# optoshield3.net
KiCad netlist of a schematic drawn in EAGLE
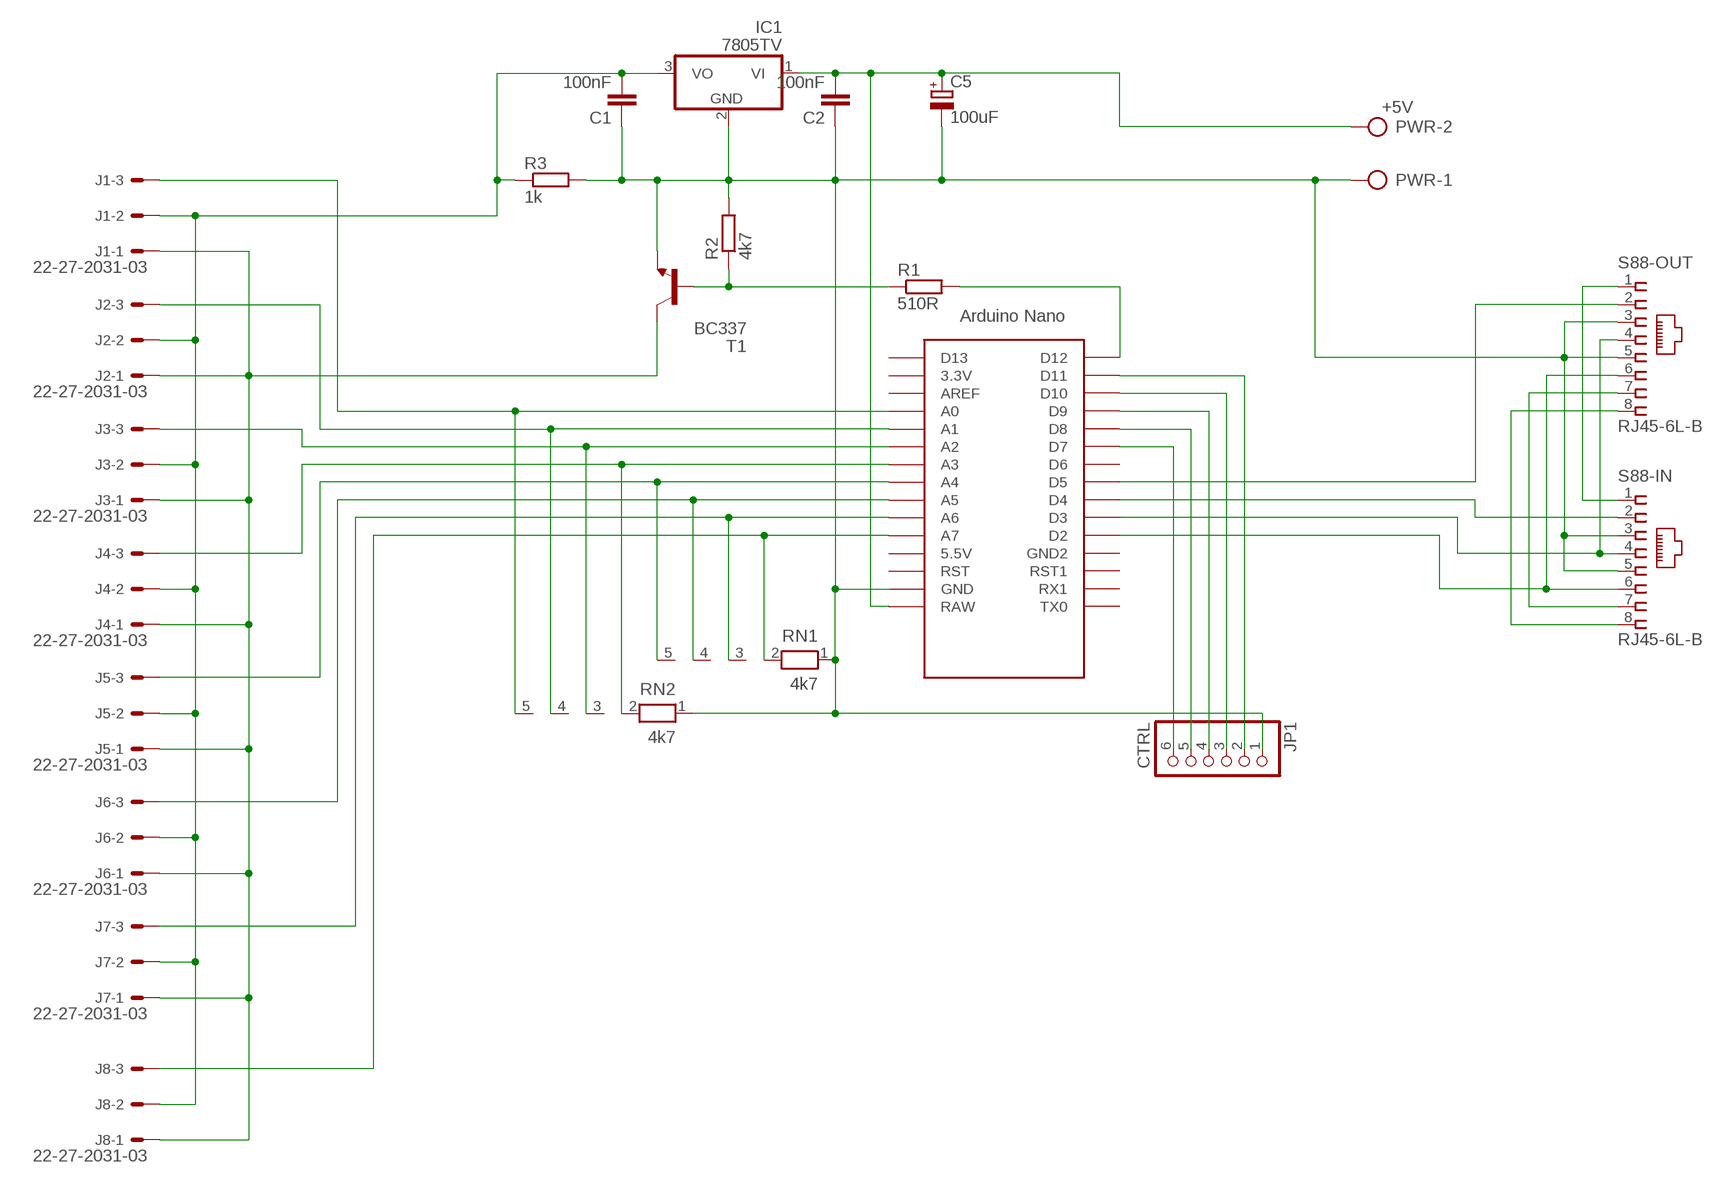
[diagram p0: schematic, sheet 1]

(export (version "E")
  (design (tool "Eeschema 10.0.6"))
  (components
    (comp (ref "C1")
      (value "100nF")
      (footprint "eagle-import:C025-025X050")
      (libsource (lib "eagle-import") (part "C-EU025-025X050"))
    )
    (comp (ref "C2")
      (value "100nF")
      (footprint "eagle-import:C025-025X050")
      (libsource (lib "eagle-import") (part "C-EU025-025X050"))
    )
    (comp (ref "C5")
      (value "100uF")
      (footprint "eagle-import:E3,5-10")
      (libsource (lib "eagle-import") (part "CPOL-EUE3.5-10"))
    )
    (comp (ref "IC1")
      (value "7805TV")
      (footprint "eagle-import:TO220V")
      (libsource (lib "eagle-import") (part "78TV05"))
    )
    (comp (ref "J1")
      (value "22-27-2031-03")
      (footprint "eagle-import:6410-03")
      (libsource (lib "eagle-import") (part "22-?-0327-2031"))
    )
    (comp (ref "J2")
      (value "22-27-2031-03")
      (footprint "eagle-import:6410-03")
      (libsource (lib "eagle-import") (part "22-?-0327-2031"))
    )
    (comp (ref "J3")
      (value "22-27-2031-03")
      (footprint "eagle-import:6410-03")
      (libsource (lib "eagle-import") (part "22-?-0327-2031"))
    )
    (comp (ref "J4")
      (value "22-27-2031-03")
      (footprint "eagle-import:6410-03")
      (libsource (lib "eagle-import") (part "22-?-0327-2031"))
    )
    (comp (ref "J5")
      (value "22-27-2031-03")
      (footprint "eagle-import:6410-03")
      (libsource (lib "eagle-import") (part "22-?-0327-2031"))
    )
    (comp (ref "J6")
      (value "22-27-2031-03")
      (footprint "eagle-import:6410-03")
      (libsource (lib "eagle-import") (part "22-?-0327-2031"))
    )
    (comp (ref "J7")
      (value "22-27-2031-03")
      (footprint "eagle-import:6410-03")
      (libsource (lib "eagle-import") (part "22-?-0327-2031"))
    )
    (comp (ref "J8")
      (value "22-27-2031-03")
      (footprint "eagle-import:6410-03")
      (libsource (lib "eagle-import") (part "22-?-0327-2031"))
    )
    (comp (ref "JP1")
      (value "CTRL")
      (footprint "eagle-import:1X06")
      (libsource (lib "eagle-import") (part "PINHD-1X6"))
    )
    (comp (ref "PWR")
      (value "+5V")
      (footprint "eagle-import:AK500_2")
      (libsource (lib "eagle-import") (part "AK500/2"))
    )
    (comp (ref "R1")
      (value "510R")
      (footprint "eagle-import:0207_10")
      (libsource (lib "eagle-import") (part "R-EU_0207/10"))
    )
    (comp (ref "R2")
      (value "4k7")
      (footprint "eagle-import:0207_10")
      (libsource (lib "eagle-import") (part "R-EU_0207/10"))
    )
    (comp (ref "R3")
      (value "1k")
      (footprint "eagle-import:0207_10")
      (libsource (lib "eagle-import") (part "resistor_R-EU_0207/10"))
    )
    (comp (ref "RN1")
      (value "4k7")
      (footprint "eagle-import:RN-5")
      (libsource (lib "eagle-import") (part "RN04"))
    )
    (comp (ref "RN2")
      (value "4k7")
      (footprint "eagle-import:RN-5")
      (libsource (lib "eagle-import") (part "RN04"))
    )
    (comp (ref "S88-IN")
      (value "RJ45-6L-B")
      (footprint "eagle-import:RJ45-NO-SHIELD")
      (libsource (lib "eagle-import") (part "RJ45-6L-B"))
    )
    (comp (ref "S88-OUT")
      (value "RJ45-6L-B")
      (footprint "eagle-import:RJ45-NO-SHIELD")
      (libsource (lib "eagle-import") (part "RJ45-6L-B"))
    )
    (comp (ref "T1")
      (value "BC337")
      (footprint "eagle-import:TO92")
      (libsource (lib "eagle-import") (part "BC337"))
    )
    (comp (ref "U$1")
      (value "NANO")
      (footprint "eagle-import:NANO")
      (libsource (lib "eagle-import") (part "NANO"))
    )
  )
  (nets
    (net (code "1") (name "Net-(IC1-GND)") (class "Default")
      (node (ref "C1") (pin "1") (pinfunction "1_1") (pintype "passive"))
      (node (ref "C2") (pin "1") (pinfunction "1_1") (pintype "passive"))
      (node (ref "C5") (pin "-") (pinfunction "-_-") (pintype "passive"))
      (node (ref "IC1") (pin "2") (pinfunction "GND_2") (pintype "passive"))
      (node (ref "JP1") (pin "1") (pinfunction "1_1") (pintype "passive"))
      (node (ref "PWR") (pin "1") (pinfunction "KL_1") (pintype "passive"))
      (node (ref "R2") (pin "2") (pinfunction "2_2") (pintype "passive"))
      (node (ref "R3") (pin "2") (pinfunction "2_2") (pintype "passive"))
      (node (ref "RN1") (pin "1") (pinfunction "1_1") (pintype "passive"))
      (node (ref "RN2") (pin "1") (pinfunction "1_1") (pintype "passive"))
      (node (ref "S88-IN") (pin "3") (pinfunction "3_3") (pintype "passive"))
      (node (ref "S88-IN") (pin "5") (pinfunction "5_5") (pintype "passive"))
      (node (ref "S88-OUT") (pin "3") (pinfunction "3_3") (pintype "passive"))
      (node (ref "S88-OUT") (pin "5") (pinfunction "5_5") (pintype "passive"))
      (node (ref "T1") (pin "1") (pinfunction "E_1") (pintype "passive"))
      (node (ref "U$1") (pin "GND") (pinfunction "GND_GND") (pintype "bidirectional"))
    )
    (net (code "2") (name "Net-(IC1-VI)") (class "Default")
      (node (ref "C2") (pin "2") (pinfunction "2_2") (pintype "passive"))
      (node (ref "C5") (pin "+") (pinfunction "+_+") (pintype "passive"))
      (node (ref "IC1") (pin "1") (pinfunction "VI_1") (pintype "input"))
      (node (ref "PWR") (pin "2") (pinfunction "KL_2") (pintype "passive"))
      (node (ref "U$1") (pin "RAW") (pinfunction "RAW_RAW") (pintype "bidirectional"))
    )
    (net (code "3") (name "Net-(IC1-VO)") (class "Default")
      (node (ref "C1") (pin "2") (pinfunction "2_2") (pintype "passive"))
      (node (ref "IC1") (pin "3") (pinfunction "VO_3") (pintype "passive"))
      (node (ref "J1") (pin "2") (pinfunction "S_2") (pintype "passive"))
      (node (ref "J2") (pin "2") (pinfunction "S_2") (pintype "passive"))
      (node (ref "J3") (pin "2") (pinfunction "S_2") (pintype "passive"))
      (node (ref "J4") (pin "2") (pinfunction "S_2") (pintype "passive"))
      (node (ref "J5") (pin "2") (pinfunction "S_2") (pintype "passive"))
      (node (ref "J6") (pin "2") (pinfunction "S_2") (pintype "passive"))
      (node (ref "J7") (pin "2") (pinfunction "S_2") (pintype "passive"))
      (node (ref "J8") (pin "2") (pinfunction "S_2") (pintype "passive"))
      (node (ref "R3") (pin "1") (pinfunction "1_1") (pintype "passive"))
    )
    (net (code "4") (name "Net-(J1A-S)") (class "Default")
      (node (ref "J1") (pin "1") (pinfunction "S_1") (pintype "passive"))
      (node (ref "J2") (pin "1") (pinfunction "S_1") (pintype "passive"))
      (node (ref "J3") (pin "1") (pinfunction "S_1") (pintype "passive"))
      (node (ref "J4") (pin "1") (pinfunction "S_1") (pintype "passive"))
      (node (ref "J5") (pin "1") (pinfunction "S_1") (pintype "passive"))
      (node (ref "J6") (pin "1") (pinfunction "S_1") (pintype "passive"))
      (node (ref "J7") (pin "1") (pinfunction "S_1") (pintype "passive"))
      (node (ref "J8") (pin "1") (pinfunction "S_1") (pintype "passive"))
      (node (ref "T1") (pin "3") (pinfunction "C_3") (pintype "passive"))
    )
    (net (code "5") (name "Net-(J1C-S)") (class "Default")
      (node (ref "J1") (pin "3") (pinfunction "S_3") (pintype "passive"))
      (node (ref "RN2") (pin "5") (pinfunction "5_5") (pintype "passive"))
      (node (ref "U$1") (pin "A0") (pinfunction "A0_A0") (pintype "bidirectional"))
    )
    (net (code "6") (name "Net-(J2C-S)") (class "Default")
      (node (ref "J2") (pin "3") (pinfunction "S_3") (pintype "passive"))
      (node (ref "RN2") (pin "4") (pinfunction "4_4") (pintype "passive"))
      (node (ref "U$1") (pin "A1") (pinfunction "A1_A1") (pintype "bidirectional"))
    )
    (net (code "7") (name "Net-(J3C-S)") (class "Default")
      (node (ref "J3") (pin "3") (pinfunction "S_3") (pintype "passive"))
      (node (ref "RN2") (pin "3") (pinfunction "3_3") (pintype "passive"))
      (node (ref "U$1") (pin "A2") (pinfunction "A2_A2") (pintype "bidirectional"))
    )
    (net (code "8") (name "Net-(J4C-S)") (class "Default")
      (node (ref "J4") (pin "3") (pinfunction "S_3") (pintype "passive"))
      (node (ref "RN2") (pin "2") (pinfunction "2_2") (pintype "passive"))
      (node (ref "U$1") (pin "A3") (pinfunction "A3_A3") (pintype "bidirectional"))
    )
    (net (code "9") (name "Net-(J5C-S)") (class "Default")
      (node (ref "J5") (pin "3") (pinfunction "S_3") (pintype "passive"))
      (node (ref "RN1") (pin "5") (pinfunction "5_5") (pintype "passive"))
      (node (ref "U$1") (pin "A4") (pinfunction "A4_A4") (pintype "bidirectional"))
    )
    (net (code "10") (name "Net-(J6C-S)") (class "Default")
      (node (ref "J6") (pin "3") (pinfunction "S_3") (pintype "passive"))
      (node (ref "RN1") (pin "4") (pinfunction "4_4") (pintype "passive"))
      (node (ref "U$1") (pin "A5") (pinfunction "A5_A5") (pintype "bidirectional"))
    )
    (net (code "11") (name "Net-(J7C-S)") (class "Default")
      (node (ref "J7") (pin "3") (pinfunction "S_3") (pintype "passive"))
      (node (ref "RN1") (pin "3") (pinfunction "3_3") (pintype "passive"))
      (node (ref "U$1") (pin "A6") (pinfunction "A6_A6") (pintype "bidirectional"))
    )
    (net (code "12") (name "Net-(J8C-S)") (class "Default")
      (node (ref "J8") (pin "3") (pinfunction "S_3") (pintype "passive"))
      (node (ref "RN1") (pin "2") (pinfunction "2_2") (pintype "passive"))
      (node (ref "U$1") (pin "A7") (pinfunction "A7_A7") (pintype "bidirectional"))
    )
    (net (code "13") (name "Net-(JP1-Pad2)") (class "Default")
      (node (ref "JP1") (pin "2") (pinfunction "2_2") (pintype "passive"))
      (node (ref "U$1") (pin "D11") (pinfunction "D11_D11") (pintype "bidirectional"))
    )
    (net (code "14") (name "Net-(JP1-Pad3)") (class "Default")
      (node (ref "JP1") (pin "3") (pinfunction "3_3") (pintype "passive"))
      (node (ref "U$1") (pin "D10") (pinfunction "D10_D10") (pintype "bidirectional"))
    )
    (net (code "15") (name "Net-(JP1-Pad4)") (class "Default")
      (node (ref "JP1") (pin "4") (pinfunction "4_4") (pintype "passive"))
      (node (ref "U$1") (pin "D9") (pinfunction "D9_D9") (pintype "bidirectional"))
    )
    (net (code "16") (name "Net-(JP1-Pad5)") (class "Default")
      (node (ref "JP1") (pin "5") (pinfunction "5_5") (pintype "passive"))
      (node (ref "U$1") (pin "D8") (pinfunction "D8_D8") (pintype "bidirectional"))
    )
    (net (code "17") (name "Net-(JP1-Pad6)") (class "Default")
      (node (ref "JP1") (pin "6") (pinfunction "6_6") (pintype "passive"))
      (node (ref "U$1") (pin "D7") (pinfunction "D7_D7") (pintype "bidirectional"))
    )
    (net (code "18") (name "Net-(R1-Pad2)") (class "Default")
      (node (ref "R1") (pin "2") (pinfunction "2_2") (pintype "passive"))
      (node (ref "U$1") (pin "D12") (pinfunction "D12_D12") (pintype "bidirectional"))
    )
    (net (code "19") (name "Net-(S88-IN-Pad1)") (class "Default")
      (node (ref "S88-IN") (pin "1") (pinfunction "1_1") (pintype "passive"))
      (node (ref "S88-OUT") (pin "1") (pinfunction "1_1") (pintype "passive"))
    )
    (net (code "20") (name "Net-(S88-IN-Pad2)") (class "Default")
      (node (ref "S88-IN") (pin "2") (pinfunction "2_2") (pintype "passive"))
      (node (ref "U$1") (pin "D4") (pinfunction "D4_D4") (pintype "bidirectional"))
    )
    (net (code "21") (name "Net-(S88-IN-Pad4)") (class "Default")
      (node (ref "S88-IN") (pin "4") (pinfunction "4_4") (pintype "passive"))
      (node (ref "S88-OUT") (pin "4") (pinfunction "4_4") (pintype "passive"))
      (node (ref "U$1") (pin "D3") (pinfunction "D3_D3") (pintype "bidirectional"))
    )
    (net (code "22") (name "Net-(S88-IN-Pad6)") (class "Default")
      (node (ref "S88-IN") (pin "6") (pinfunction "6_6") (pintype "passive"))
      (node (ref "S88-OUT") (pin "6") (pinfunction "6_6") (pintype "passive"))
      (node (ref "U$1") (pin "D2") (pinfunction "D2_D2") (pintype "bidirectional"))
    )
    (net (code "23") (name "Net-(S88-IN-Pad7)") (class "Default")
      (node (ref "S88-IN") (pin "7") (pinfunction "7_7") (pintype "passive"))
      (node (ref "S88-OUT") (pin "7") (pinfunction "7_7") (pintype "passive"))
    )
    (net (code "24") (name "Net-(S88-IN-Pad8)") (class "Default")
      (node (ref "S88-IN") (pin "8") (pinfunction "8_8") (pintype "passive"))
      (node (ref "S88-OUT") (pin "8") (pinfunction "8_8") (pintype "passive"))
    )
    (net (code "25") (name "Net-(S88-OUT-Pad2)") (class "Default")
      (node (ref "S88-OUT") (pin "2") (pinfunction "2_2") (pintype "passive"))
      (node (ref "U$1") (pin "D5") (pinfunction "D5_D5") (pintype "bidirectional"))
    )
    (net (code "26") (name "Net-(T1-B)") (class "Default")
      (node (ref "R1") (pin "1") (pinfunction "1_1") (pintype "passive"))
      (node (ref "R2") (pin "1") (pinfunction "1_1") (pintype "passive"))
      (node (ref "T1") (pin "2") (pinfunction "B_2") (pintype "passive"))
    )
    (net (code "27") (name "unconnected-(U$1-5.5V-Pad5V)") (class "Default")
      (node (ref "U$1") (pin "5V") (pinfunction "5.5V_5V") (pintype "bidirectional"))
    )
    (net (code "28") (name "unconnected-(U$1-GND2-PadGND1)") (class "Default")
      (node (ref "U$1") (pin "GND1") (pinfunction "GND2_GND1") (pintype "bidirectional"))
    )
    (net (code "29") (name "unconnected-(U$1-Pad3.3V)") (class "Default")
      (node (ref "U$1") (pin "3.3V") (pinfunction "3.3V_3.3V") (pintype "bidirectional"))
    )
    (net (code "30") (name "unconnected-(U$1-PadAREF)") (class "Default")
      (node (ref "U$1") (pin "AREF") (pinfunction "AREF_AREF") (pintype "bidirectional"))
    )
    (net (code "31") (name "unconnected-(U$1-PadD6)") (class "Default")
      (node (ref "U$1") (pin "D6") (pinfunction "D6_D6") (pintype "bidirectional"))
    )
    (net (code "32") (name "unconnected-(U$1-PadD13)") (class "Default")
      (node (ref "U$1") (pin "D13") (pinfunction "D13_D13") (pintype "bidirectional"))
    )
    (net (code "33") (name "unconnected-(U$1-PadICSP1)") (class "Default")
      (node (ref "U$1") (pin "ICSP1") (pinfunction "ICSP1_ICSP1") (pintype "bidirectional"))
    )
    (net (code "34") (name "unconnected-(U$1-PadICSP2)") (class "Default")
      (node (ref "U$1") (pin "ICSP2") (pinfunction "ICSP2_ICSP2") (pintype "bidirectional"))
    )
    (net (code "35") (name "unconnected-(U$1-PadICSP3)") (class "Default")
      (node (ref "U$1") (pin "ICSP3") (pinfunction "ICSP3_ICSP3") (pintype "bidirectional"))
    )
    (net (code "36") (name "unconnected-(U$1-PadICSP4)") (class "Default")
      (node (ref "U$1") (pin "ICSP4") (pinfunction "ICSP4_ICSP4") (pintype "bidirectional"))
    )
    (net (code "37") (name "unconnected-(U$1-PadICSP5)") (class "Default")
      (node (ref "U$1") (pin "ICSP5") (pinfunction "ICSP5_ICSP5") (pintype "bidirectional"))
    )
    (net (code "38") (name "unconnected-(U$1-PadICSP6)") (class "Default")
      (node (ref "U$1") (pin "ICSP6") (pinfunction "ICSP6_ICSP6") (pintype "bidirectional"))
    )
    (net (code "39") (name "unconnected-(U$1-PadRST)") (class "Default")
      (node (ref "U$1") (pin "RST") (pinfunction "RST_RST") (pintype "bidirectional"))
    )
    (net (code "40") (name "unconnected-(U$1-PadRST1)") (class "Default")
      (node (ref "U$1") (pin "RST1") (pinfunction "RST1_RST1") (pintype "bidirectional"))
    )
    (net (code "41") (name "unconnected-(U$1-PadRX1)") (class "Default")
      (node (ref "U$1") (pin "RX1") (pinfunction "RX1_RX1") (pintype "bidirectional"))
    )
    (net (code "42") (name "unconnected-(U$1-PadTX0)") (class "Default")
      (node (ref "U$1") (pin "TX0") (pinfunction "TX0_TX0") (pintype "bidirectional"))
    )
  )
)
